# mainboard-raspi-4.net
KiCad netlist of a schematic drawn in EAGLE
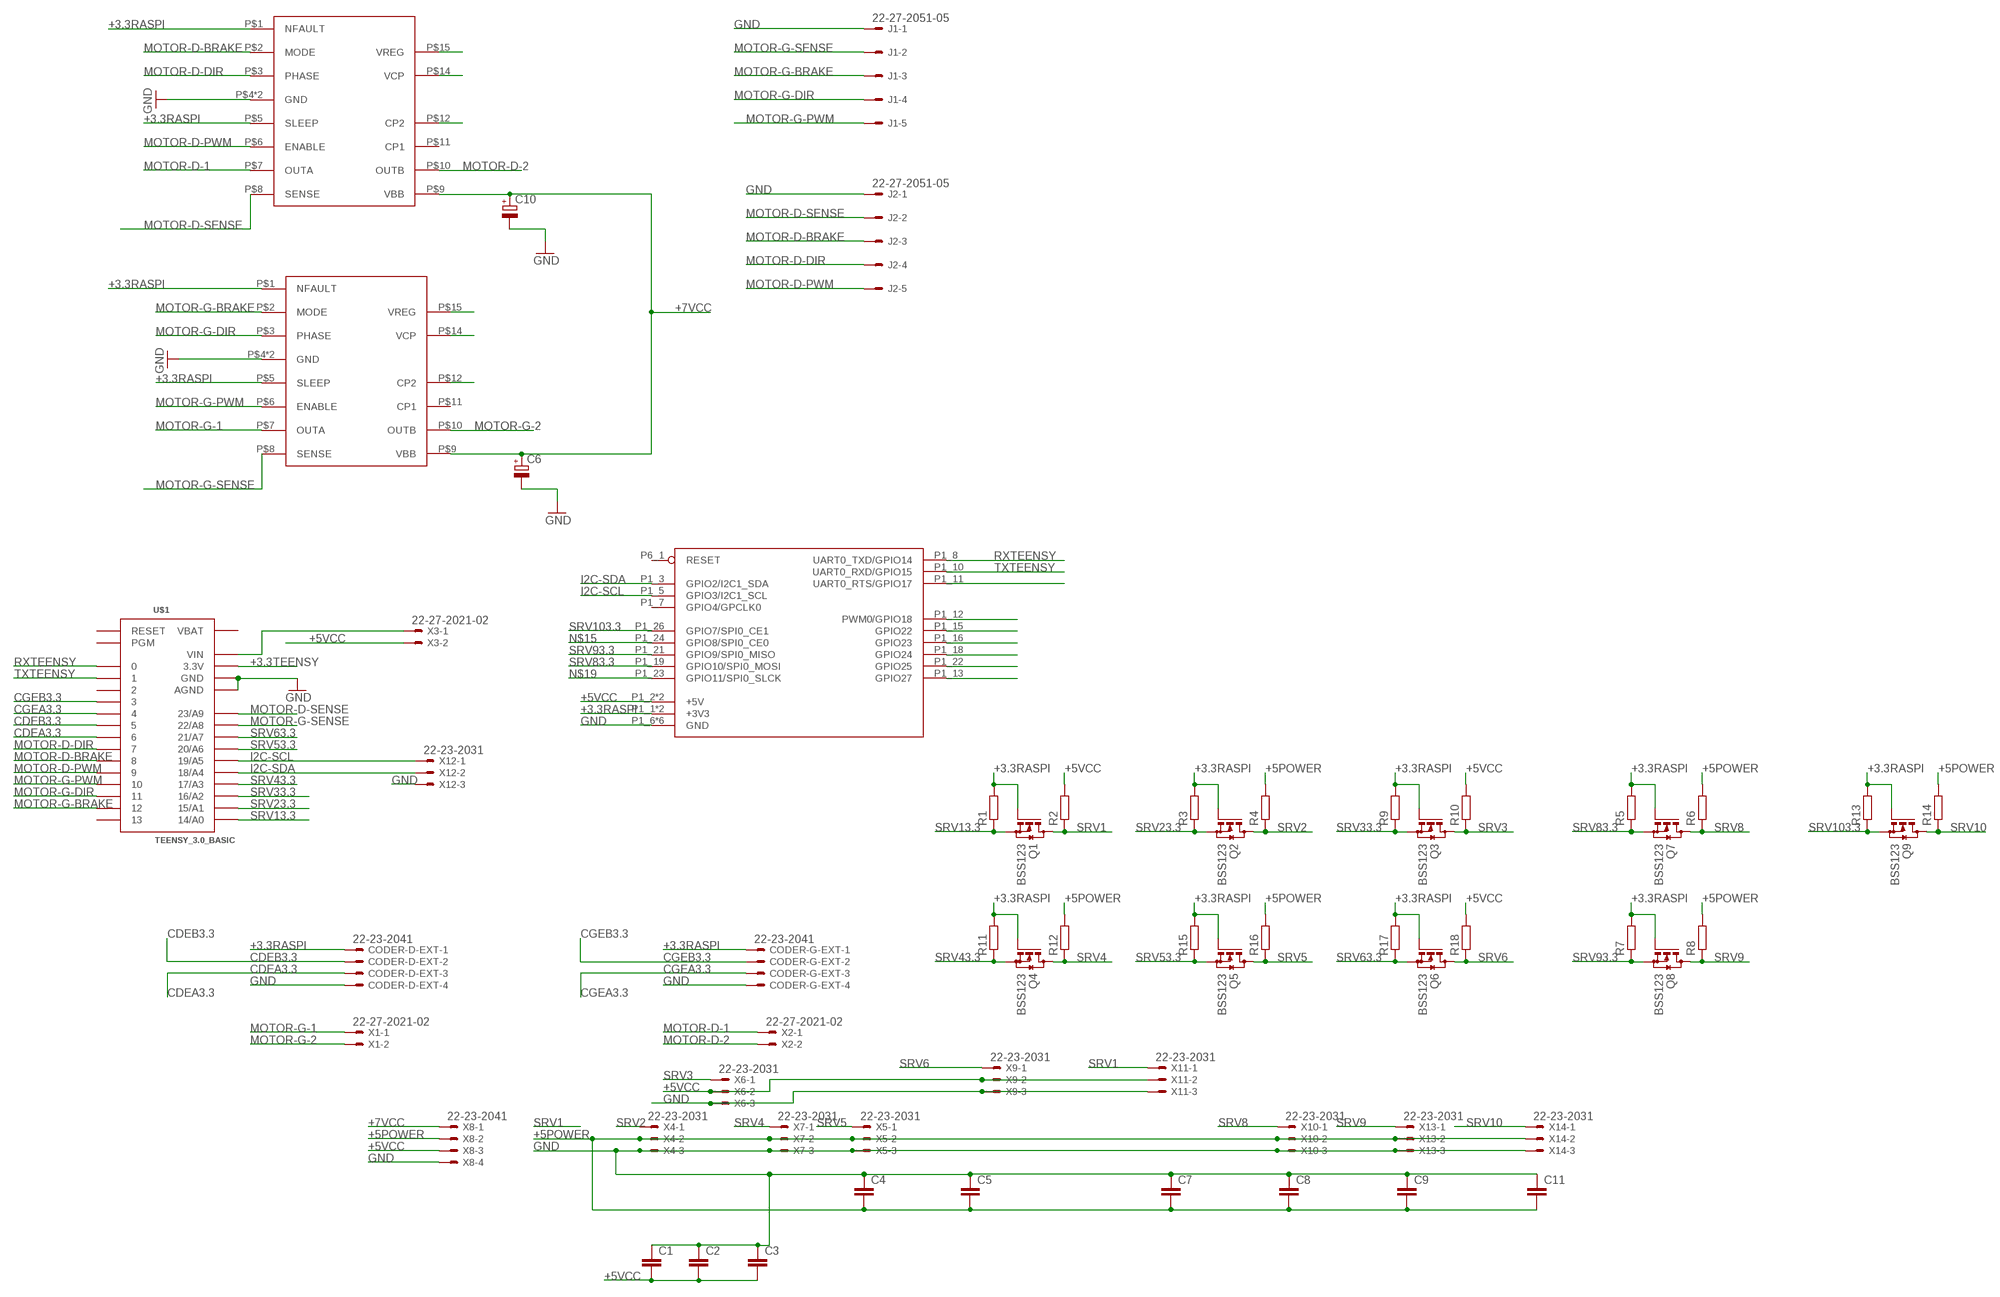
[diagram p0: schematic, sheet 1]

(export (version "E")
  (design (tool "Eeschema 10.0.6"))
  (components
    (comp (ref "C1")
      (value "C-EUC0603K")
      (footprint "eagle-import:C0603K")
      (libsource (lib "eagle-import") (part "C-EUC0603K"))
    )
    (comp (ref "C2")
      (value "C-EUC0603K")
      (footprint "eagle-import:C0603K")
      (libsource (lib "eagle-import") (part "C-EUC0603K"))
    )
    (comp (ref "C3")
      (value "C-EUC0603K")
      (footprint "eagle-import:C0603K")
      (libsource (lib "eagle-import") (part "C-EUC0603K"))
    )
    (comp (ref "C4")
      (value "C-EUC0603K")
      (footprint "eagle-import:C0603K")
      (libsource (lib "eagle-import") (part "C-EUC0603K"))
    )
    (comp (ref "C5")
      (value "C-EUC0603K")
      (footprint "eagle-import:C0603K")
      (libsource (lib "eagle-import") (part "C-EUC0603K"))
    )
    (comp (ref "C6")
      (value "CPOL-EUE3.5-8")
      (footprint "eagle-import:E3,5-8")
      (libsource (lib "eagle-import") (part "CPOL-EUE3.5-8"))
    )
    (comp (ref "C7")
      (value "C-EUC0603K")
      (footprint "eagle-import:C0603K")
      (libsource (lib "eagle-import") (part "C-EUC0603K"))
    )
    (comp (ref "C8")
      (value "C-EUC0603K")
      (footprint "eagle-import:C0603K")
      (libsource (lib "eagle-import") (part "C-EUC0603K"))
    )
    (comp (ref "C9")
      (value "C-EUC0603K")
      (footprint "eagle-import:C0603K")
      (libsource (lib "eagle-import") (part "C-EUC0603K"))
    )
    (comp (ref "C10")
      (value "CPOL-EUE3.5-8")
      (footprint "eagle-import:E3,5-8")
      (libsource (lib "eagle-import") (part "CPOL-EUE3.5-8"))
    )
    (comp (ref "C11")
      (value "C-EUC0603K")
      (footprint "eagle-import:C0603K")
      (libsource (lib "eagle-import") (part "C-EUC0603K"))
    )
    (comp (ref "CODER-D-EXT")
      (value "22-23-2041")
      (footprint "eagle-import:22-23-2041")
      (fields (field (name "MF") "MOLEX"))
      (libsource (lib "eagle-import") (part "22-23-2041"))
    )
    (comp (ref "CODER-G-EXT")
      (value "22-23-2041")
      (footprint "eagle-import:22-23-2041")
      (fields (field (name "MF") "MOLEX"))
      (libsource (lib "eagle-import") (part "22-23-2041"))
    )
    (comp (ref "J1")
      (value "22-27-2051-05")
      (footprint "eagle-import:6410-05")
      (libsource (lib "eagle-import") (part "22-?-0527-2051"))
    )
    (comp (ref "J2")
      (value "22-27-2051-05")
      (footprint "eagle-import:6410-05")
      (libsource (lib "eagle-import") (part "22-?-0527-2051"))
    )
    (comp (ref "Q1")
      (value "BSS123")
      (footprint "eagle-import:SOT23")
      (libsource (lib "eagle-import") (part "BSS123"))
    )
    (comp (ref "Q2")
      (value "BSS123")
      (footprint "eagle-import:SOT23")
      (libsource (lib "eagle-import") (part "BSS123"))
    )
    (comp (ref "Q3")
      (value "BSS123")
      (footprint "eagle-import:SOT23")
      (libsource (lib "eagle-import") (part "BSS123"))
    )
    (comp (ref "Q4")
      (value "BSS123")
      (footprint "eagle-import:SOT23")
      (libsource (lib "eagle-import") (part "BSS123"))
    )
    (comp (ref "Q5")
      (value "BSS123")
      (footprint "eagle-import:SOT23")
      (libsource (lib "eagle-import") (part "BSS123"))
    )
    (comp (ref "Q6")
      (value "BSS123")
      (footprint "eagle-import:SOT23")
      (libsource (lib "eagle-import") (part "BSS123"))
    )
    (comp (ref "Q7")
      (value "BSS123")
      (footprint "eagle-import:SOT23")
      (libsource (lib "eagle-import") (part "BSS123"))
    )
    (comp (ref "Q8")
      (value "BSS123")
      (footprint "eagle-import:SOT23")
      (libsource (lib "eagle-import") (part "BSS123"))
    )
    (comp (ref "Q9")
      (value "BSS123")
      (footprint "eagle-import:SOT23")
      (libsource (lib "eagle-import") (part "BSS123"))
    )
    (comp (ref "R1")
      (value "R-EU_R0603")
      (footprint "eagle-import:R0603")
      (libsource (lib "eagle-import") (part "R-EU_R0603"))
    )
    (comp (ref "R2")
      (value "R-EU_R0603")
      (footprint "eagle-import:R0603")
      (libsource (lib "eagle-import") (part "R-EU_R0603"))
    )
    (comp (ref "R3")
      (value "R-EU_R0603")
      (footprint "eagle-import:R0603")
      (libsource (lib "eagle-import") (part "R-EU_R0603"))
    )
    (comp (ref "R4")
      (value "R-EU_R0603")
      (footprint "eagle-import:R0603")
      (libsource (lib "eagle-import") (part "R-EU_R0603"))
    )
    (comp (ref "R5")
      (value "R-EU_R0603")
      (footprint "eagle-import:R0603")
      (libsource (lib "eagle-import") (part "R-EU_R0603"))
    )
    (comp (ref "R6")
      (value "R-EU_R0603")
      (footprint "eagle-import:R0603")
      (libsource (lib "eagle-import") (part "R-EU_R0603"))
    )
    (comp (ref "R7")
      (value "R-EU_R0603")
      (footprint "eagle-import:R0603")
      (libsource (lib "eagle-import") (part "R-EU_R0603"))
    )
    (comp (ref "R8")
      (value "R-EU_R0603")
      (footprint "eagle-import:R0603")
      (libsource (lib "eagle-import") (part "R-EU_R0603"))
    )
    (comp (ref "R9")
      (value "R-EU_R0603")
      (footprint "eagle-import:R0603")
      (libsource (lib "eagle-import") (part "R-EU_R0603"))
    )
    (comp (ref "R10")
      (value "R-EU_R0603")
      (footprint "eagle-import:R0603")
      (libsource (lib "eagle-import") (part "R-EU_R0603"))
    )
    (comp (ref "R11")
      (value "R-EU_R0603")
      (footprint "eagle-import:R0603")
      (libsource (lib "eagle-import") (part "R-EU_R0603"))
    )
    (comp (ref "R12")
      (value "R-EU_R0603")
      (footprint "eagle-import:R0603")
      (libsource (lib "eagle-import") (part "R-EU_R0603"))
    )
    (comp (ref "R13")
      (value "R-EU_R0603")
      (footprint "eagle-import:R0603")
      (libsource (lib "eagle-import") (part "R-EU_R0603"))
    )
    (comp (ref "R14")
      (value "R-EU_R0603")
      (footprint "eagle-import:R0603")
      (libsource (lib "eagle-import") (part "R-EU_R0603"))
    )
    (comp (ref "R15")
      (value "R-EU_R0603")
      (footprint "eagle-import:R0603")
      (libsource (lib "eagle-import") (part "R-EU_R0603"))
    )
    (comp (ref "R16")
      (value "R-EU_R0603")
      (footprint "eagle-import:R0603")
      (libsource (lib "eagle-import") (part "R-EU_R0603"))
    )
    (comp (ref "R17")
      (value "R-EU_R0603")
      (footprint "eagle-import:R0603")
      (libsource (lib "eagle-import") (part "R-EU_R0603"))
    )
    (comp (ref "R18")
      (value "R-EU_R0603")
      (footprint "eagle-import:R0603")
      (libsource (lib "eagle-import") (part "R-EU_R0603"))
    )
    (comp (ref "U$1")
      (value "TEENSY_3.0_BASIC")
      (footprint "eagle-import:TEENSY_3.0_BASIC")
      (libsource (lib "eagle-import") (part "TEENSY_3.0_BASIC"))
    )
    (comp (ref "U$2")
      (value "RPI-B-V2SHIELD")
      (footprint "eagle-import:RPI-B-V2-SHIELD")
      (libsource (lib "eagle-import") (part "RPI-B-V2SHIELD"))
    )
    (comp (ref "U$3")
      (value "A3950-DIL")
      (footprint "eagle-import:DIL16")
      (libsource (lib "eagle-import") (part "A3950-DIL"))
    )
    (comp (ref "U$4")
      (value "A3950-DIL")
      (footprint "eagle-import:DIL16")
      (libsource (lib "eagle-import") (part "A3950-DIL"))
    )
    (comp (ref "X1")
      (value "22-27-2021-02")
      (footprint "eagle-import:6410-02")
      (libsource (lib "eagle-import") (part "22-?-0227-2021"))
    )
    (comp (ref "X2")
      (value "22-27-2021-02")
      (footprint "eagle-import:6410-02")
      (libsource (lib "eagle-import") (part "22-?-0227-2021"))
    )
    (comp (ref "X3")
      (value "22-27-2021-02")
      (footprint "eagle-import:6410-02")
      (libsource (lib "eagle-import") (part "22-?-0227-2021"))
    )
    (comp (ref "X4")
      (value "22-23-2031")
      (footprint "eagle-import:22-23-2031")
      (fields (field (name "MF") "MOLEX"))
      (libsource (lib "eagle-import") (part "22-23-2031"))
    )
    (comp (ref "X5")
      (value "22-23-2031")
      (footprint "eagle-import:22-23-2031")
      (fields (field (name "MF") "MOLEX"))
      (libsource (lib "eagle-import") (part "22-23-2031"))
    )
    (comp (ref "X6")
      (value "22-23-2031")
      (footprint "eagle-import:22-23-2031")
      (fields (field (name "MF") "MOLEX"))
      (libsource (lib "eagle-import") (part "22-23-2031"))
    )
    (comp (ref "X7")
      (value "22-23-2031")
      (footprint "eagle-import:22-23-2031")
      (fields (field (name "MF") "MOLEX"))
      (libsource (lib "eagle-import") (part "22-23-2031"))
    )
    (comp (ref "X8")
      (value "22-23-2041")
      (footprint "eagle-import:22-23-2041")
      (fields (field (name "MF") "MOLEX"))
      (libsource (lib "eagle-import") (part "22-23-2041"))
    )
    (comp (ref "X9")
      (value "22-23-2031")
      (footprint "eagle-import:22-23-2031")
      (fields (field (name "MF") "MOLEX"))
      (libsource (lib "eagle-import") (part "22-23-2031"))
    )
    (comp (ref "X10")
      (value "22-23-2031")
      (footprint "eagle-import:22-23-2031")
      (fields (field (name "MF") "MOLEX"))
      (libsource (lib "eagle-import") (part "22-23-2031"))
    )
    (comp (ref "X11")
      (value "22-23-2031")
      (footprint "eagle-import:22-23-2031")
      (fields (field (name "MF") "MOLEX"))
      (libsource (lib "eagle-import") (part "22-23-2031"))
    )
    (comp (ref "X12")
      (value "22-23-2031")
      (footprint "eagle-import:22-23-2031")
      (fields (field (name "MF") "MOLEX"))
      (libsource (lib "eagle-import") (part "22-23-2031"))
    )
    (comp (ref "X13")
      (value "22-23-2031")
      (footprint "eagle-import:22-23-2031")
      (fields (field (name "MF") "MOLEX"))
      (libsource (lib "eagle-import") (part "22-23-2031"))
    )
    (comp (ref "X14")
      (value "22-23-2031")
      (footprint "eagle-import:22-23-2031")
      (fields (field (name "MF") "MOLEX"))
      (libsource (lib "eagle-import") (part "22-23-2031"))
    )
  )
  (nets
    (net (code "1") (name "/+3.3RASPI") (class "Default")
      (node (ref "CODER-D-EXT") (pin "1") (pinfunction "S_1") (pintype "passive"))
      (node (ref "CODER-G-EXT") (pin "1") (pinfunction "S_1") (pintype "passive"))
      (node (ref "Q1") (pin "1") (pinfunction "G_1") (pintype "passive"))
      (node (ref "Q2") (pin "1") (pinfunction "G_1") (pintype "passive"))
      (node (ref "Q3") (pin "1") (pinfunction "G_1") (pintype "passive"))
      (node (ref "Q4") (pin "1") (pinfunction "G_1") (pintype "passive"))
      (node (ref "Q5") (pin "1") (pinfunction "G_1") (pintype "passive"))
      (node (ref "Q6") (pin "1") (pinfunction "G_1") (pintype "passive"))
      (node (ref "Q7") (pin "1") (pinfunction "G_1") (pintype "passive"))
      (node (ref "Q8") (pin "1") (pinfunction "G_1") (pintype "passive"))
      (node (ref "Q9") (pin "1") (pinfunction "G_1") (pintype "passive"))
      (node (ref "R1") (pin "2") (pinfunction "2_2") (pintype "passive"))
      (node (ref "R11") (pin "2") (pinfunction "2_2") (pintype "passive"))
      (node (ref "R13") (pin "2") (pinfunction "2_2") (pintype "passive"))
      (node (ref "R15") (pin "2") (pinfunction "2_2") (pintype "passive"))
      (node (ref "R17") (pin "2") (pinfunction "2_2") (pintype "passive"))
      (node (ref "R3") (pin "2") (pinfunction "2_2") (pintype "passive"))
      (node (ref "R5") (pin "2") (pinfunction "2_2") (pintype "passive"))
      (node (ref "R7") (pin "2") (pinfunction "2_2") (pintype "passive"))
      (node (ref "R9") (pin "2") (pinfunction "2_2") (pintype "passive"))
      (node (ref "U$2") (pin "P1_1") (pinfunction "+3V3_P1_1") (pintype "power_in"))
      (node (ref "U$2") (pin "P1_17") (pinfunction "+3V3_P1_17") (pintype "power_in"))
      (node (ref "U$3") (pin "P$1") (pinfunction "NFAULT_P$1") (pintype "bidirectional"))
      (node (ref "U$3") (pin "P$5") (pinfunction "SLEEP_P$5") (pintype "bidirectional"))
      (node (ref "U$4") (pin "P$1") (pinfunction "NFAULT_P$1") (pintype "bidirectional"))
      (node (ref "U$4") (pin "P$5") (pinfunction "SLEEP_P$5") (pintype "bidirectional"))
    )
    (net (code "2") (name "/+3.3TEENSY") (class "Default")
      (node (ref "U$1") (pin "3.3V") (pinfunction "3.3V_3.3V") (pintype "power_in"))
      (node (ref "U$1") (pin "3.3V1") (pinfunction "3.3V_3.3V1") (pintype "power_in"))
    )
    (net (code "3") (name "/+5POWER") (class "Default")
      (node (ref "C11") (pin "2") (pinfunction "2_2") (pintype "passive"))
      (node (ref "C4") (pin "2") (pinfunction "2_2") (pintype "passive"))
      (node (ref "C5") (pin "2") (pinfunction "2_2") (pintype "passive"))
      (node (ref "C7") (pin "2") (pinfunction "2_2") (pintype "passive"))
      (node (ref "C8") (pin "2") (pinfunction "2_2") (pintype "passive"))
      (node (ref "C9") (pin "2") (pinfunction "2_2") (pintype "passive"))
      (node (ref "R12") (pin "2") (pinfunction "2_2") (pintype "passive"))
      (node (ref "R14") (pin "2") (pinfunction "2_2") (pintype "passive"))
      (node (ref "R16") (pin "2") (pinfunction "2_2") (pintype "passive"))
      (node (ref "R4") (pin "2") (pinfunction "2_2") (pintype "passive"))
      (node (ref "R6") (pin "2") (pinfunction "2_2") (pintype "passive"))
      (node (ref "R8") (pin "2") (pinfunction "2_2") (pintype "passive"))
      (node (ref "X10") (pin "2") (pinfunction "S_2") (pintype "passive"))
      (node (ref "X13") (pin "2") (pinfunction "S_2") (pintype "passive"))
      (node (ref "X14") (pin "2") (pinfunction "S_2") (pintype "passive"))
      (node (ref "X4") (pin "2") (pinfunction "S_2") (pintype "passive"))
      (node (ref "X5") (pin "2") (pinfunction "S_2") (pintype "passive"))
      (node (ref "X7") (pin "2") (pinfunction "S_2") (pintype "passive"))
      (node (ref "X8") (pin "2") (pinfunction "S_2") (pintype "passive"))
    )
    (net (code "4") (name "/+5VCC") (class "Default")
      (node (ref "C1") (pin "2") (pinfunction "2_2") (pintype "passive"))
      (node (ref "C2") (pin "2") (pinfunction "2_2") (pintype "passive"))
      (node (ref "C3") (pin "2") (pinfunction "2_2") (pintype "passive"))
      (node (ref "R10") (pin "2") (pinfunction "2_2") (pintype "passive"))
      (node (ref "R18") (pin "2") (pinfunction "2_2") (pintype "passive"))
      (node (ref "R2") (pin "2") (pinfunction "2_2") (pintype "passive"))
      (node (ref "U$2") (pin "P1_2") (pinfunction "+5V_P1_2") (pintype "power_in"))
      (node (ref "U$2") (pin "P1_4") (pinfunction "+5V_P1_4") (pintype "power_in"))
      (node (ref "X11") (pin "2") (pinfunction "S_2") (pintype "passive"))
      (node (ref "X3") (pin "2") (pinfunction "S_2") (pintype "passive"))
      (node (ref "X6") (pin "2") (pinfunction "S_2") (pintype "passive"))
      (node (ref "X8") (pin "3") (pinfunction "S_3") (pintype "passive"))
      (node (ref "X9") (pin "2") (pinfunction "S_2") (pintype "passive"))
    )
    (net (code "5") (name "/+7VCC") (class "Default")
      (node (ref "C10") (pin "+") (pinfunction "+_+") (pintype "passive"))
      (node (ref "C6") (pin "+") (pinfunction "+_+") (pintype "passive"))
      (node (ref "U$3") (pin "P$9") (pinfunction "VBB_P$9") (pintype "bidirectional"))
      (node (ref "U$4") (pin "P$9") (pinfunction "VBB_P$9") (pintype "bidirectional"))
      (node (ref "X8") (pin "1") (pinfunction "S_1") (pintype "passive"))
    )
    (net (code "6") (name "/CDEA3.3") (class "Default")
      (node (ref "CODER-D-EXT") (pin "3") (pinfunction "S_3") (pintype "passive"))
      (node (ref "U$1") (pin "6") (pinfunction "6_6") (pintype "bidirectional"))
    )
    (net (code "7") (name "/CDEB3.3") (class "Default")
      (node (ref "CODER-D-EXT") (pin "2") (pinfunction "S_2") (pintype "passive"))
      (node (ref "U$1") (pin "5") (pinfunction "5_5") (pintype "bidirectional"))
    )
    (net (code "8") (name "/CGEA3.3") (class "Default")
      (node (ref "CODER-G-EXT") (pin "3") (pinfunction "S_3") (pintype "passive"))
      (node (ref "U$1") (pin "4") (pinfunction "4_4") (pintype "bidirectional"))
    )
    (net (code "9") (name "/CGEB3.3") (class "Default")
      (node (ref "CODER-G-EXT") (pin "2") (pinfunction "S_2") (pintype "passive"))
      (node (ref "U$1") (pin "3") (pinfunction "3_3") (pintype "bidirectional"))
    )
    (net (code "10") (name "/I2C-SCL") (class "Default")
      (node (ref "U$1") (pin "19/A5") (pinfunction "19/A5_19/A5") (pintype "bidirectional"))
      (node (ref "U$2") (pin "P1_5") (pinfunction "GPIO3/I2C1_SCL_P1_5") (pintype "bidirectional"))
      (node (ref "X12") (pin "1") (pinfunction "S_1") (pintype "passive"))
    )
    (net (code "11") (name "/I2C-SDA") (class "Default")
      (node (ref "U$1") (pin "18/A4") (pinfunction "18/A4_18/A4") (pintype "bidirectional"))
      (node (ref "U$2") (pin "P1_3") (pinfunction "GPIO2/I2C1_SDA_P1_3") (pintype "bidirectional"))
      (node (ref "X12") (pin "2") (pinfunction "S_2") (pintype "passive"))
    )
    (net (code "12") (name "/MOTOR-D-1") (class "Default")
      (node (ref "U$4") (pin "P$7") (pinfunction "OUTA_P$7") (pintype "bidirectional"))
      (node (ref "X2") (pin "1") (pinfunction "S_1") (pintype "passive"))
    )
    (net (code "13") (name "/MOTOR-D-2") (class "Default")
      (node (ref "U$4") (pin "P$10") (pinfunction "OUTB_P$10") (pintype "bidirectional"))
      (node (ref "X2") (pin "2") (pinfunction "S_2") (pintype "passive"))
    )
    (net (code "14") (name "/MOTOR-D-BRAKE") (class "Default")
      (node (ref "J2") (pin "3") (pinfunction "S_3") (pintype "passive"))
      (node (ref "U$1") (pin "8") (pinfunction "8_8") (pintype "bidirectional"))
      (node (ref "U$4") (pin "P$2") (pinfunction "MODE_P$2") (pintype "bidirectional"))
    )
    (net (code "15") (name "/MOTOR-D-DIR") (class "Default")
      (node (ref "J2") (pin "4") (pinfunction "S_4") (pintype "passive"))
      (node (ref "U$1") (pin "7") (pinfunction "7_7") (pintype "bidirectional"))
      (node (ref "U$4") (pin "P$3") (pinfunction "PHASE_P$3") (pintype "bidirectional"))
    )
    (net (code "16") (name "/MOTOR-D-PWM") (class "Default")
      (node (ref "J2") (pin "5") (pinfunction "S_5") (pintype "passive"))
      (node (ref "U$1") (pin "9") (pinfunction "9_9") (pintype "bidirectional"))
      (node (ref "U$4") (pin "P$6") (pinfunction "ENABLE_P$6") (pintype "bidirectional"))
    )
    (net (code "17") (name "/MOTOR-D-SENSE") (class "Default")
      (node (ref "J2") (pin "2") (pinfunction "S_2") (pintype "passive"))
      (node (ref "U$1") (pin "23/A9") (pinfunction "23/A9_23/A9") (pintype "bidirectional"))
      (node (ref "U$4") (pin "P$8") (pinfunction "SENSE_P$8") (pintype "bidirectional"))
    )
    (net (code "18") (name "/MOTOR-G-1") (class "Default")
      (node (ref "U$3") (pin "P$7") (pinfunction "OUTA_P$7") (pintype "bidirectional"))
      (node (ref "X1") (pin "1") (pinfunction "S_1") (pintype "passive"))
    )
    (net (code "19") (name "/MOTOR-G-2") (class "Default")
      (node (ref "U$3") (pin "P$10") (pinfunction "OUTB_P$10") (pintype "bidirectional"))
      (node (ref "X1") (pin "2") (pinfunction "S_2") (pintype "passive"))
    )
    (net (code "20") (name "/MOTOR-G-BRAKE") (class "Default")
      (node (ref "J1") (pin "3") (pinfunction "S_3") (pintype "passive"))
      (node (ref "U$1") (pin "12") (pinfunction "12_12") (pintype "bidirectional"))
      (node (ref "U$3") (pin "P$2") (pinfunction "MODE_P$2") (pintype "bidirectional"))
    )
    (net (code "21") (name "/MOTOR-G-DIR") (class "Default")
      (node (ref "J1") (pin "4") (pinfunction "S_4") (pintype "passive"))
      (node (ref "U$1") (pin "11") (pinfunction "11_11") (pintype "bidirectional"))
      (node (ref "U$3") (pin "P$3") (pinfunction "PHASE_P$3") (pintype "bidirectional"))
    )
    (net (code "22") (name "/MOTOR-G-PWM") (class "Default")
      (node (ref "J1") (pin "5") (pinfunction "S_5") (pintype "passive"))
      (node (ref "U$1") (pin "10") (pinfunction "10_10") (pintype "bidirectional"))
      (node (ref "U$3") (pin "P$6") (pinfunction "ENABLE_P$6") (pintype "bidirectional"))
    )
    (net (code "23") (name "/MOTOR-G-SENSE") (class "Default")
      (node (ref "J1") (pin "2") (pinfunction "S_2") (pintype "passive"))
      (node (ref "U$1") (pin "22/A8") (pinfunction "22/A8_22/A8") (pintype "bidirectional"))
      (node (ref "U$3") (pin "P$8") (pinfunction "SENSE_P$8") (pintype "bidirectional"))
    )
    (net (code "24") (name "/N$15") (class "Default")
      (node (ref "U$2") (pin "P1_24") (pinfunction "GPIO8/SPI0_CE0_P1_24") (pintype "bidirectional"))
    )
    (net (code "25") (name "/N$19") (class "Default")
      (node (ref "U$2") (pin "P1_23") (pinfunction "GPIO11/SPI0_SLCK_P1_23") (pintype "bidirectional"))
    )
    (net (code "26") (name "/RESET") (class "Default")
      (node (ref "U$2") (pin "P6_1") (pinfunction "RESET_P6_1") (pintype "power_in"))
    )
    (net (code "27") (name "/RXTEENSY") (class "Default")
      (node (ref "U$1") (pin "0") (pinfunction "0_0") (pintype "bidirectional"))
      (node (ref "U$2") (pin "P1_8") (pinfunction "UART0_TXD/GPIO14_P1_8") (pintype "bidirectional"))
    )
    (net (code "28") (name "/SRV1") (class "Default")
      (node (ref "Q1") (pin "3") (pinfunction "D_3") (pintype "passive"))
      (node (ref "R2") (pin "1") (pinfunction "1_1") (pintype "passive"))
      (node (ref "X11") (pin "1") (pinfunction "S_1") (pintype "passive"))
    )
    (net (code "29") (name "/SRV2") (class "Default")
      (node (ref "Q2") (pin "3") (pinfunction "D_3") (pintype "passive"))
      (node (ref "R4") (pin "1") (pinfunction "1_1") (pintype "passive"))
      (node (ref "X4") (pin "1") (pinfunction "S_1") (pintype "passive"))
    )
    (net (code "30") (name "/SRV3") (class "Default")
      (node (ref "Q3") (pin "3") (pinfunction "D_3") (pintype "passive"))
      (node (ref "R10") (pin "1") (pinfunction "1_1") (pintype "passive"))
      (node (ref "X6") (pin "1") (pinfunction "S_1") (pintype "passive"))
    )
    (net (code "31") (name "/SRV4") (class "Default")
      (node (ref "Q4") (pin "3") (pinfunction "D_3") (pintype "passive"))
      (node (ref "R12") (pin "1") (pinfunction "1_1") (pintype "passive"))
      (node (ref "X7") (pin "1") (pinfunction "S_1") (pintype "passive"))
    )
    (net (code "32") (name "/SRV5") (class "Default")
      (node (ref "Q5") (pin "3") (pinfunction "D_3") (pintype "passive"))
      (node (ref "R16") (pin "1") (pinfunction "1_1") (pintype "passive"))
      (node (ref "X5") (pin "1") (pinfunction "S_1") (pintype "passive"))
    )
    (net (code "33") (name "/SRV6") (class "Default")
      (node (ref "Q6") (pin "3") (pinfunction "D_3") (pintype "passive"))
      (node (ref "R18") (pin "1") (pinfunction "1_1") (pintype "passive"))
      (node (ref "X9") (pin "1") (pinfunction "S_1") (pintype "passive"))
    )
    (net (code "34") (name "/SRV8") (class "Default")
      (node (ref "Q7") (pin "3") (pinfunction "D_3") (pintype "passive"))
      (node (ref "R6") (pin "1") (pinfunction "1_1") (pintype "passive"))
      (node (ref "X10") (pin "1") (pinfunction "S_1") (pintype "passive"))
    )
    (net (code "35") (name "/SRV9") (class "Default")
      (node (ref "Q8") (pin "3") (pinfunction "D_3") (pintype "passive"))
      (node (ref "R8") (pin "1") (pinfunction "1_1") (pintype "passive"))
      (node (ref "X13") (pin "1") (pinfunction "S_1") (pintype "passive"))
    )
    (net (code "36") (name "/SRV10") (class "Default")
      (node (ref "Q9") (pin "3") (pinfunction "D_3") (pintype "passive"))
      (node (ref "R14") (pin "1") (pinfunction "1_1") (pintype "passive"))
      (node (ref "X14") (pin "1") (pinfunction "S_1") (pintype "passive"))
    )
    (net (code "37") (name "/SRV13.3") (class "Default")
      (node (ref "Q1") (pin "2") (pinfunction "S_2") (pintype "passive"))
      (node (ref "R1") (pin "1") (pinfunction "1_1") (pintype "passive"))
      (node (ref "U$1") (pin "14/A0") (pinfunction "14/A0_14/A0") (pintype "bidirectional"))
    )
    (net (code "38") (name "/SRV23.3") (class "Default")
      (node (ref "Q2") (pin "2") (pinfunction "S_2") (pintype "passive"))
      (node (ref "R3") (pin "1") (pinfunction "1_1") (pintype "passive"))
      (node (ref "U$1") (pin "15/A1") (pinfunction "15/A1_15/A1") (pintype "bidirectional"))
    )
    (net (code "39") (name "/SRV33.3") (class "Default")
      (node (ref "Q3") (pin "2") (pinfunction "S_2") (pintype "passive"))
      (node (ref "R9") (pin "1") (pinfunction "1_1") (pintype "passive"))
      (node (ref "U$1") (pin "16/A2") (pinfunction "16/A2_16/A2") (pintype "bidirectional"))
    )
    (net (code "40") (name "/SRV43.3") (class "Default")
      (node (ref "Q4") (pin "2") (pinfunction "S_2") (pintype "passive"))
      (node (ref "R11") (pin "1") (pinfunction "1_1") (pintype "passive"))
      (node (ref "U$1") (pin "17/A3") (pinfunction "17/A3_17/A3") (pintype "bidirectional"))
    )
    (net (code "41") (name "/SRV53.3") (class "Default")
      (node (ref "Q5") (pin "2") (pinfunction "S_2") (pintype "passive"))
      (node (ref "R15") (pin "1") (pinfunction "1_1") (pintype "passive"))
      (node (ref "U$1") (pin "20/A6") (pinfunction "20/A6_20/A6") (pintype "bidirectional"))
    )
    (net (code "42") (name "/SRV63.3") (class "Default")
      (node (ref "Q6") (pin "2") (pinfunction "S_2") (pintype "passive"))
      (node (ref "R17") (pin "1") (pinfunction "1_1") (pintype "passive"))
      (node (ref "U$1") (pin "21/A7") (pinfunction "21/A7_21/A7") (pintype "bidirectional"))
    )
    (net (code "43") (name "/SRV83.3") (class "Default")
      (node (ref "Q7") (pin "2") (pinfunction "S_2") (pintype "passive"))
      (node (ref "R5") (pin "1") (pinfunction "1_1") (pintype "passive"))
      (node (ref "U$2") (pin "P1_19") (pinfunction "GPIO10/SPI0_MOSI_P1_19") (pintype "bidirectional"))
    )
    (net (code "44") (name "/SRV93.3") (class "Default")
      (node (ref "Q8") (pin "2") (pinfunction "S_2") (pintype "passive"))
      (node (ref "R7") (pin "1") (pinfunction "1_1") (pintype "passive"))
      (node (ref "U$2") (pin "P1_21") (pinfunction "GPIO9/SPI0_MISO_P1_21") (pintype "bidirectional"))
    )
    (net (code "45") (name "/SRV103.3") (class "Default")
      (node (ref "Q9") (pin "2") (pinfunction "S_2") (pintype "passive"))
      (node (ref "R13") (pin "1") (pinfunction "1_1") (pintype "passive"))
      (node (ref "U$2") (pin "P1_26") (pinfunction "GPIO7/SPI0_CE1_P1_26") (pintype "bidirectional"))
    )
    (net (code "46") (name "/TXTEENSY") (class "Default")
      (node (ref "U$1") (pin "1") (pinfunction "1_1") (pintype "bidirectional"))
      (node (ref "U$2") (pin "P1_10") (pinfunction "UART0_RXD/GPIO15_P1_10") (pintype "bidirectional"))
    )
    (net (code "47") (name "/VBAT") (class "Default")
      (node (ref "U$1") (pin "VBAT") (pinfunction "VBAT_VBAT") (pintype "power_in"))
    )
    (net (code "48") (name "GND") (class "Default")
      (node (ref "C1") (pin "1") (pinfunction "1_1") (pintype "passive"))
      (node (ref "C10") (pin "-") (pinfunction "-_-") (pintype "passive"))
      (node (ref "C11") (pin "1") (pinfunction "1_1") (pintype "passive"))
      (node (ref "C2") (pin "1") (pinfunction "1_1") (pintype "passive"))
      (node (ref "C3") (pin "1") (pinfunction "1_1") (pintype "passive"))
      (node (ref "C4") (pin "1") (pinfunction "1_1") (pintype "passive"))
      (node (ref "C5") (pin "1") (pinfunction "1_1") (pintype "passive"))
      (node (ref "C6") (pin "-") (pinfunction "-_-") (pintype "passive"))
      (node (ref "C7") (pin "1") (pinfunction "1_1") (pintype "passive"))
      (node (ref "C8") (pin "1") (pinfunction "1_1") (pintype "passive"))
      (node (ref "C9") (pin "1") (pinfunction "1_1") (pintype "passive"))
      (node (ref "CODER-D-EXT") (pin "4") (pinfunction "S_4") (pintype "passive"))
      (node (ref "CODER-G-EXT") (pin "4") (pinfunction "S_4") (pintype "passive"))
      (node (ref "J1") (pin "1") (pinfunction "S_1") (pintype "passive"))
      (node (ref "J2") (pin "1") (pinfunction "S_1") (pintype "passive"))
      (node (ref "U$1") (pin "AGND") (pinfunction "AGND_AGND") (pintype "power_in"))
      (node (ref "U$1") (pin "GND") (pinfunction "GND_GND") (pintype "power_in"))
      (node (ref "U$1") (pin "GND1") (pinfunction "GND_GND1") (pintype "power_in"))
      (node (ref "U$2") (pin "P1_14") (pinfunction "GND_P1_14") (pintype "power_in"))
      (node (ref "U$2") (pin "P1_20") (pinfunction "GND_P1_20") (pintype "power_in"))
      (node (ref "U$2") (pin "P1_25") (pinfunction "GND_P1_25") (pintype "power_in"))
      (node (ref "U$2") (pin "P1_6") (pinfunction "GND_P1_6") (pintype "power_in"))
      (node (ref "U$2") (pin "P1_9") (pinfunction "GND_P1_9") (pintype "power_in"))
      (node (ref "U$2") (pin "P6_2") (pinfunction "GND_P6_2") (pintype "power_in"))
      (node (ref "U$3") (pin "P$13") (pinfunction "GND_P$13") (pintype "bidirectional"))
      (node (ref "U$3") (pin "P$4") (pinfunction "GND_P$4") (pintype "bidirectional"))
      (node (ref "U$4") (pin "P$13") (pinfunction "GND_P$13") (pintype "bidirectional"))
      (node (ref "U$4") (pin "P$4") (pinfunction "GND_P$4") (pintype "bidirectional"))
      (node (ref "X10") (pin "3") (pinfunction "S_3") (pintype "passive"))
      (node (ref "X11") (pin "3") (pinfunction "S_3") (pintype "passive"))
      (node (ref "X12") (pin "3") (pinfunction "S_3") (pintype "passive"))
      (node (ref "X13") (pin "3") (pinfunction "S_3") (pintype "passive"))
      (node (ref "X14") (pin "3") (pinfunction "S_3") (pintype "passive"))
      (node (ref "X4") (pin "3") (pinfunction "S_3") (pintype "passive"))
      (node (ref "X5") (pin "3") (pinfunction "S_3") (pintype "passive"))
      (node (ref "X6") (pin "3") (pinfunction "S_3") (pintype "passive"))
      (node (ref "X7") (pin "3") (pinfunction "S_3") (pintype "passive"))
      (node (ref "X8") (pin "4") (pinfunction "S_4") (pintype "passive"))
      (node (ref "X9") (pin "3") (pinfunction "S_3") (pintype "passive"))
    )
    (net (code "49") (name "Net-(X3A-S)") (class "Default")
      (node (ref "U$1") (pin "VIN") (pinfunction "VIN_VIN") (pintype "power_in"))
      (node (ref "X3") (pin "1") (pinfunction "S_1") (pintype "passive"))
    )
    (net (code "50") (name "unconnected-(U$1-Pad2)") (class "Default")
      (node (ref "U$1") (pin "2") (pinfunction "2_2") (pintype "bidirectional"))
    )
    (net (code "51") (name "unconnected-(U$1-Pad13)") (class "Default")
      (node (ref "U$1") (pin "13") (pinfunction "13_13") (pintype "bidirectional"))
    )
    (net (code "52") (name "unconnected-(U$1-PadPGM)") (class "Default")
      (node (ref "U$1") (pin "PGM") (pinfunction "PGM_PGM") (pintype "bidirectional"))
    )
    (net (code "53") (name "unconnected-(U$1-PadRESET)") (class "Default")
      (node (ref "U$1") (pin "RESET") (pinfunction "RESET_RESET") (pintype "bidirectional"))
    )
    (net (code "54") (name "unconnected-(U$2-GPIO4{slash}GPCLK0-PadP1_7)") (class "Default")
      (node (ref "U$2") (pin "P1_7") (pinfunction "GPIO4/GPCLK0_P1_7") (pintype "bidirectional"))
    )
    (net (code "55") (name "unconnected-(U$2-GPIO22-PadP1_15)") (class "Default")
      (node (ref "U$2") (pin "P1_15") (pinfunction "GPIO22_P1_15") (pintype "bidirectional"))
    )
    (net (code "56") (name "unconnected-(U$2-GPIO23-PadP1_16)") (class "Default")
      (node (ref "U$2") (pin "P1_16") (pinfunction "GPIO23_P1_16") (pintype "bidirectional"))
    )
    (net (code "57") (name "unconnected-(U$2-GPIO24-PadP1_18)") (class "Default")
      (node (ref "U$2") (pin "P1_18") (pinfunction "GPIO24_P1_18") (pintype "bidirectional"))
    )
    (net (code "58") (name "unconnected-(U$2-GPIO25-PadP1_22)") (class "Default")
      (node (ref "U$2") (pin "P1_22") (pinfunction "GPIO25_P1_22") (pintype "bidirectional"))
    )
    (net (code "59") (name "unconnected-(U$2-GPIO27-PadP1_13)") (class "Default")
      (node (ref "U$2") (pin "P1_13") (pinfunction "GPIO27_P1_13") (pintype "bidirectional"))
    )
    (net (code "60") (name "unconnected-(U$2-PWM0{slash}GPIO18-PadP1_12)") (class "Default")
      (node (ref "U$2") (pin "P1_12") (pinfunction "PWM0/GPIO18_P1_12") (pintype "bidirectional"))
    )
    (net (code "61") (name "unconnected-(U$2-UART0_RTS{slash}GPIO17-PadP1_11)") (class "Default")
      (node (ref "U$2") (pin "P1_11") (pinfunction "UART0_RTS/GPIO17_P1_11") (pintype "bidirectional"))
    )
    (net (code "62") (name "unconnected-(U$3-CP1-PadP$11)") (class "Default")
      (node (ref "U$3") (pin "P$11") (pinfunction "CP1_P$11") (pintype "bidirectional"))
    )
    (net (code "63") (name "unconnected-(U$3-CP2-PadP$12)") (class "Default")
      (node (ref "U$3") (pin "P$12") (pinfunction "CP2_P$12") (pintype "bidirectional"))
    )
    (net (code "64") (name "unconnected-(U$3-VCP-PadP$14)") (class "Default")
      (node (ref "U$3") (pin "P$14") (pinfunction "VCP_P$14") (pintype "bidirectional"))
    )
    (net (code "65") (name "unconnected-(U$3-VREG-PadP$15)") (class "Default")
      (node (ref "U$3") (pin "P$15") (pinfunction "VREG_P$15") (pintype "bidirectional"))
    )
    (net (code "66") (name "unconnected-(U$4-CP1-PadP$11)") (class "Default")
      (node (ref "U$4") (pin "P$11") (pinfunction "CP1_P$11") (pintype "bidirectional"))
    )
    (net (code "67") (name "unconnected-(U$4-CP2-PadP$12)") (class "Default")
      (node (ref "U$4") (pin "P$12") (pinfunction "CP2_P$12") (pintype "bidirectional"))
    )
    (net (code "68") (name "unconnected-(U$4-VCP-PadP$14)") (class "Default")
      (node (ref "U$4") (pin "P$14") (pinfunction "VCP_P$14") (pintype "bidirectional"))
    )
    (net (code "69") (name "unconnected-(U$4-VREG-PadP$15)") (class "Default")
      (node (ref "U$4") (pin "P$15") (pinfunction "VREG_P$15") (pintype "bidirectional"))
    )
  )
)
